# storage_board.net
KiCad netlist of a schematic drawn in EAGLE
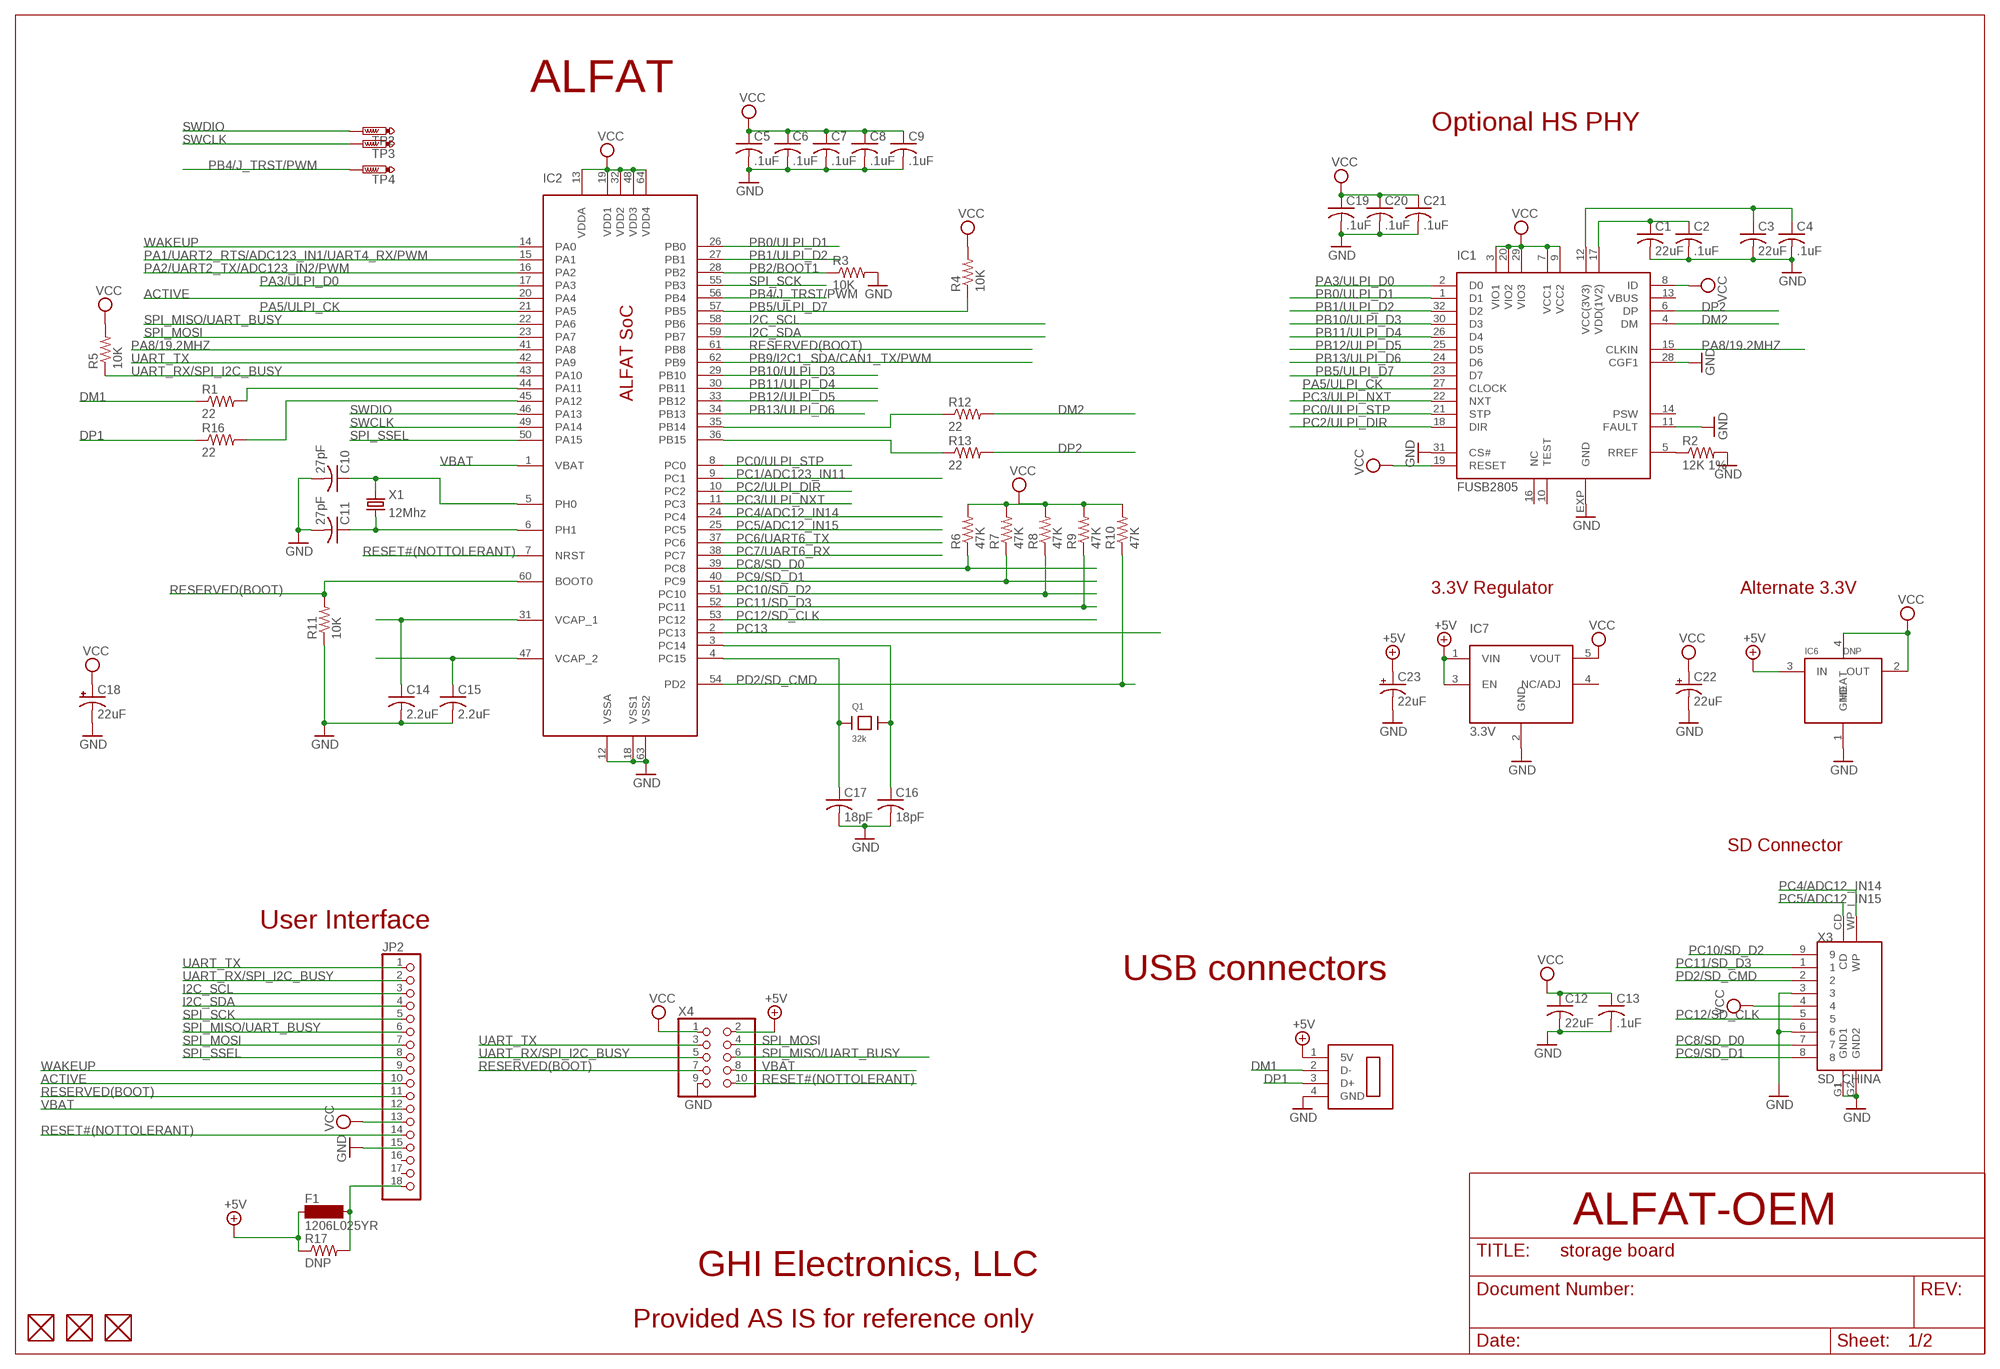
[diagram p0: schematic, sheet 1]
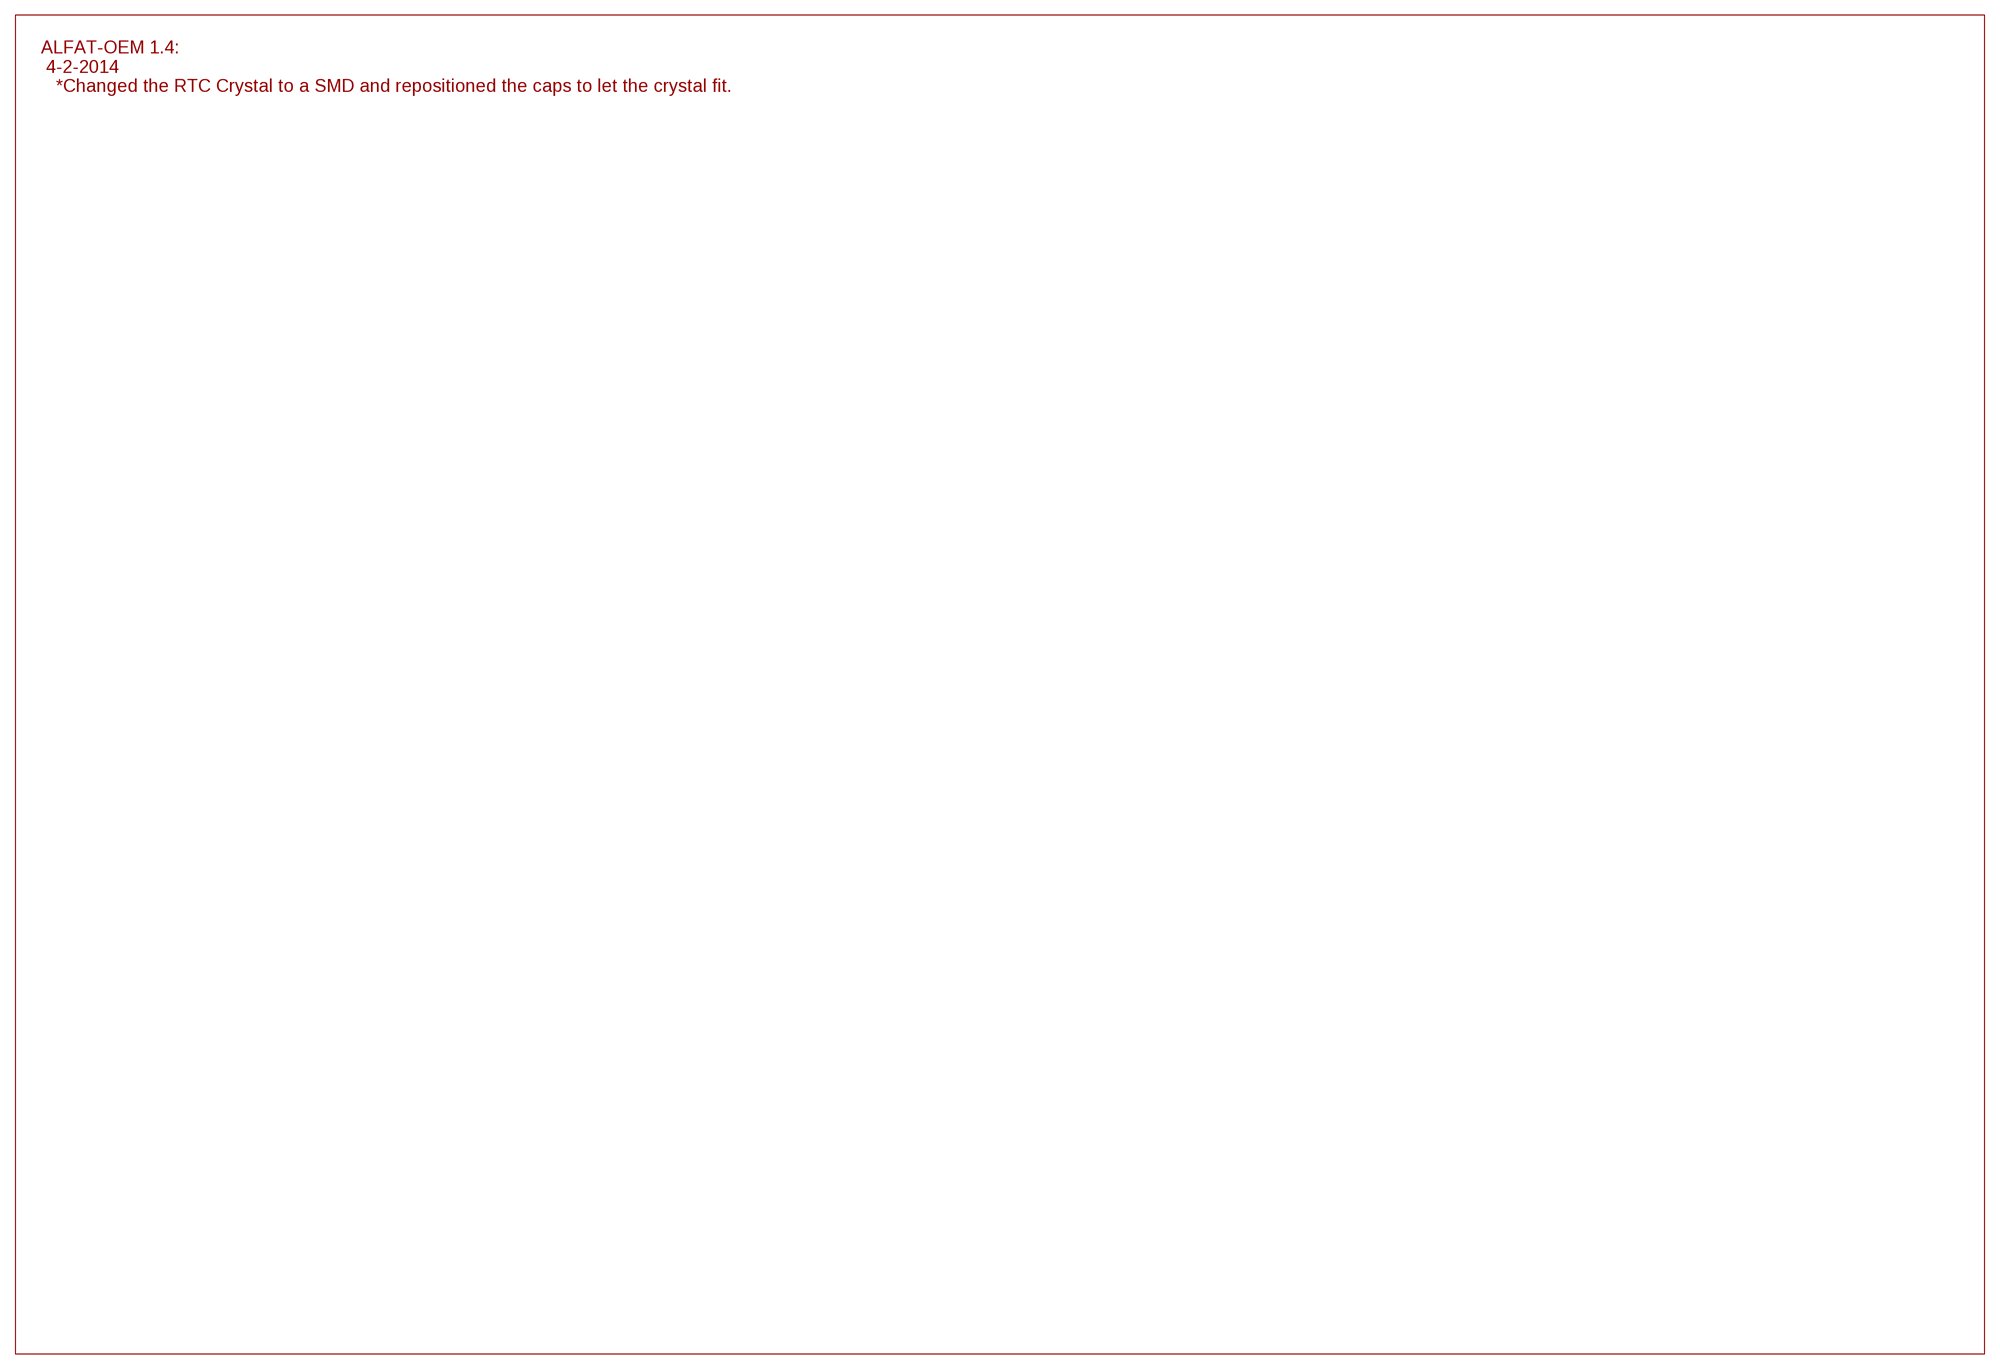
[diagram p1: schematic, sheet 2]

(export (version "E")
  (design (tool "Eeschema 10.0.6"))
  (components
    (comp (ref "C1")
      (value "22uF")
      (footprint "eagle-import:C0805K")
      (libsource (lib "eagle-import") (part "C-USC0805K"))
    )
    (comp (ref "C2")
      (value ".1uF")
      (footprint "eagle-import:C0603K")
      (libsource (lib "eagle-import") (part "C-USC0603K"))
    )
    (comp (ref "C3")
      (value "22uF")
      (footprint "eagle-import:C0805K")
      (libsource (lib "eagle-import") (part "C-USC0805K"))
    )
    (comp (ref "C4")
      (value ".1uF")
      (footprint "eagle-import:C0603K")
      (libsource (lib "eagle-import") (part "C-USC0603K"))
    )
    (comp (ref "C5")
      (value ".1uF")
      (footprint "eagle-import:C0603K")
      (libsource (lib "eagle-import") (part "C-USC0603K"))
    )
    (comp (ref "C6")
      (value ".1uF")
      (footprint "eagle-import:C0603K")
      (libsource (lib "eagle-import") (part "C-USC0603K"))
    )
    (comp (ref "C7")
      (value ".1uF")
      (footprint "eagle-import:C0603K")
      (libsource (lib "eagle-import") (part "C-USC0603K"))
    )
    (comp (ref "C8")
      (value ".1uF")
      (footprint "eagle-import:C0603K")
      (libsource (lib "eagle-import") (part "C-USC0603K"))
    )
    (comp (ref "C9")
      (value ".1uF")
      (footprint "eagle-import:C0603K")
      (libsource (lib "eagle-import") (part "C-USC0603K"))
    )
    (comp (ref "C10")
      (value "27pF")
      (footprint "eagle-import:C0603K")
      (libsource (lib "eagle-import") (part "C-USC0603K"))
    )
    (comp (ref "C11")
      (value "27pF")
      (footprint "eagle-import:C0603K")
      (libsource (lib "eagle-import") (part "C-USC0603K"))
    )
    (comp (ref "C12")
      (value "22uF")
      (footprint "eagle-import:C0805K")
      (libsource (lib "eagle-import") (part "C-USC0805K"))
    )
    (comp (ref "C13")
      (value ".1uF")
      (footprint "eagle-import:C0603K")
      (libsource (lib "eagle-import") (part "C-USC0603K"))
    )
    (comp (ref "C14")
      (value "2.2uF")
      (footprint "eagle-import:C0805K")
      (libsource (lib "eagle-import") (part "C-USC0805K"))
    )
    (comp (ref "C15")
      (value "2.2uF")
      (footprint "eagle-import:C0805K")
      (libsource (lib "eagle-import") (part "C-USC0805K"))
    )
    (comp (ref "C16")
      (value "18pF")
      (footprint "eagle-import:C0603K")
      (libsource (lib "eagle-import") (part "C-USC0603K"))
    )
    (comp (ref "C17")
      (value "18pF")
      (footprint "eagle-import:C0603K")
      (libsource (lib "eagle-import") (part "C-USC0603K"))
    )
    (comp (ref "C18")
      (value "22uF")
      (footprint "eagle-import:CT3528")
      (libsource (lib "eagle-import") (part "CPOL-USCT3528"))
    )
    (comp (ref "C19")
      (value ".1uF")
      (footprint "eagle-import:C0603K")
      (libsource (lib "eagle-import") (part "C-USC0603K"))
    )
    (comp (ref "C20")
      (value ".1uF")
      (footprint "eagle-import:C0603K")
      (libsource (lib "eagle-import") (part "C-USC0603K"))
    )
    (comp (ref "C21")
      (value ".1uF")
      (footprint "eagle-import:C0603K")
      (libsource (lib "eagle-import") (part "C-USC0603K"))
    )
    (comp (ref "C22")
      (value "22uF")
      (footprint "eagle-import:CT3528")
      (libsource (lib "eagle-import") (part "CPOL-USCT3528"))
    )
    (comp (ref "C23")
      (value "22uF")
      (footprint "eagle-import:CT3528")
      (libsource (lib "eagle-import") (part "CPOL-USCT3528"))
    )
    (comp (ref "F1")
      (value "1206L025YR")
      (footprint "eagle-import:SM-1206")
      (libsource (lib "eagle-import") (part "SM-1206"))
    )
    (comp (ref "FUD1")
      (value "FIDUCIAL")
      (footprint "eagle-import:FIDUCIAL_40MIL")
      (libsource (lib "eagle-import") (part "FIDUCIAL"))
    )
    (comp (ref "FUD2")
      (value "FIDUCIAL")
      (footprint "eagle-import:FIDUCIAL_40MIL")
      (libsource (lib "eagle-import") (part "FIDUCIAL"))
    )
    (comp (ref "FUD3")
      (value "FIDUCIAL")
      (footprint "eagle-import:FIDUCIAL_40MIL")
      (libsource (lib "eagle-import") (part "FIDUCIAL"))
    )
    (comp (ref "IC1")
      (value "FUSB2805")
      (footprint "eagle-import:MLP32")
      (libsource (lib "eagle-import") (part "FUSB2805"))
    )
    (comp (ref "IC2")
      (value "STM32F40X")
      (footprint "eagle-import:LQFP64")
      (libsource (lib "eagle-import") (part "STM32F40X"))
    )
    (comp (ref "IC6")
      (value "DNP")
      (footprint "eagle-import:SOT89")
      (libsource (lib "eagle-import") (part "LD1117SOT89"))
    )
    (comp (ref "IC7")
      (value "3.3V")
      (footprint "eagle-import:SOT23-5")
      (libsource (lib "eagle-import") (part "5PIN_REG"))
    )
    (comp (ref "JP2")
      (value "PINHD-1X18")
      (footprint "eagle-import:1X18")
      (libsource (lib "eagle-import") (part "PINHD-1X18"))
    )
    (comp (ref "Q1")
      (value "32k")
      (footprint "eagle-import:CRYSTAL_3.2X1.5")
      (libsource (lib "eagle-import") (part "CRYSTAL_3.2X1.5"))
    )
    (comp (ref "R1")
      (value "22")
      (footprint "eagle-import:R0603")
      (libsource (lib "eagle-import") (part "R-US_R0603"))
    )
    (comp (ref "R2")
      (value "12K 1%")
      (footprint "eagle-import:R0603")
      (libsource (lib "eagle-import") (part "R-US_R0603"))
    )
    (comp (ref "R3")
      (value "10K")
      (footprint "eagle-import:R0603")
      (libsource (lib "eagle-import") (part "R-US_R0603"))
    )
    (comp (ref "R4")
      (value "10K")
      (footprint "eagle-import:R0603")
      (libsource (lib "eagle-import") (part "R-US_R0603"))
    )
    (comp (ref "R5")
      (value "10K")
      (footprint "eagle-import:R0603")
      (libsource (lib "eagle-import") (part "R-US_R0603"))
    )
    (comp (ref "R6")
      (value "47K")
      (footprint "eagle-import:R0603")
      (libsource (lib "eagle-import") (part "R-US_R0603"))
    )
    (comp (ref "R7")
      (value "47K")
      (footprint "eagle-import:R0603")
      (libsource (lib "eagle-import") (part "R-US_R0603"))
    )
    (comp (ref "R8")
      (value "47K")
      (footprint "eagle-import:R0603")
      (libsource (lib "eagle-import") (part "R-US_R0603"))
    )
    (comp (ref "R9")
      (value "47K")
      (footprint "eagle-import:R0603")
      (libsource (lib "eagle-import") (part "R-US_R0603"))
    )
    (comp (ref "R10")
      (value "47K")
      (footprint "eagle-import:R0603")
      (libsource (lib "eagle-import") (part "R-US_R0603"))
    )
    (comp (ref "R11")
      (value "10K")
      (footprint "eagle-import:R0603")
      (libsource (lib "eagle-import") (part "R-US_R0603"))
    )
    (comp (ref "R12")
      (value "22")
      (footprint "eagle-import:R0603")
      (libsource (lib "eagle-import") (part "R-US_R0603"))
    )
    (comp (ref "R13")
      (value "22")
      (footprint "eagle-import:R0603")
      (libsource (lib "eagle-import") (part "R-US_R0603"))
    )
    (comp (ref "R16")
      (value "22")
      (footprint "eagle-import:R0603")
      (libsource (lib "eagle-import") (part "R-US_R0603"))
    )
    (comp (ref "R17")
      (value "DNP")
      (footprint "eagle-import:R0603")
      (libsource (lib "eagle-import") (part "R-US_R0603"))
    )
    (comp (ref "TP2")
      (value "PTR1B1,27")
      (footprint "eagle-import:B1,27")
      (libsource (lib "eagle-import") (part "PTR1B1,27"))
    )
    (comp (ref "TP3")
      (value "PTR1B1,27")
      (footprint "eagle-import:B1,27")
      (libsource (lib "eagle-import") (part "PTR1B1,27"))
    )
    (comp (ref "TP4")
      (value "PTR1B1,27")
      (footprint "eagle-import:B1,27")
      (libsource (lib "eagle-import") (part "PTR1B1,27"))
    )
    (comp (ref "X1")
      (value "12Mhz")
      (footprint "eagle-import:SM49@1")
      (libsource (lib "eagle-import") (part "CRYTALSM49"))
    )
    (comp (ref "X2")
      (value "USB_HOST_CON")
      (footprint "eagle-import:USB_HOST_CON")
      (libsource (lib "eagle-import") (part "USB_HOST_CON"))
    )
    (comp (ref "X3")
      (value "SD_CHINA")
      (footprint "eagle-import:SD_CHINA")
      (libsource (lib "eagle-import") (part "SD_CHINA"))
    )
    (comp (ref "X4")
      (value "PINHD-2X5")
      (footprint "eagle-import:2X05")
      (libsource (lib "eagle-import") (part "PINHD-2X5"))
    )
  )
  (nets
    (net (code "1") (name "+5V") (class "Default")
      (node (ref "C23") (pin "+") (pinfunction "+_+") (pintype "passive"))
      (node (ref "F1") (pin "1") (pinfunction "1_1") (pintype "passive"))
      (node (ref "IC6") (pin "3") (pinfunction "IN_3") (pintype "bidirectional"))
      (node (ref "IC7") (pin "1") (pinfunction "VIN_1") (pintype "bidirectional"))
      (node (ref "IC7") (pin "3") (pinfunction "EN_3") (pintype "bidirectional"))
      (node (ref "R17") (pin "1") (pinfunction "1_1") (pintype "passive"))
      (node (ref "X2") (pin "1") (pinfunction "5V_1") (pintype "input"))
      (node (ref "X4") (pin "2") (pinfunction "2_2") (pintype "passive"))
    )
    (net (code "2") (name "ACTIVE") (class "Default")
      (node (ref "IC2") (pin "20") (pinfunction "PA4_20") (pintype "bidirectional"))
      (node (ref "JP2") (pin "10") (pinfunction "10_10") (pintype "passive"))
    )
    (net (code "3") (name "DM1") (class "Default")
      (node (ref "R1") (pin "1") (pinfunction "1_1") (pintype "passive"))
      (node (ref "X2") (pin "2") (pinfunction "D-_2") (pintype "bidirectional"))
    )
    (net (code "4") (name "DM2") (class "Default")
      (node (ref "IC1") (pin "4") (pinfunction "DM_4") (pintype "bidirectional"))
      (node (ref "R12") (pin "2") (pinfunction "2_2") (pintype "passive"))
    )
    (net (code "5") (name "DP1") (class "Default")
      (node (ref "R16") (pin "1") (pinfunction "1_1") (pintype "passive"))
      (node (ref "X2") (pin "3") (pinfunction "D+_3") (pintype "bidirectional"))
    )
    (net (code "6") (name "DP2") (class "Default")
      (node (ref "IC1") (pin "6") (pinfunction "DP_6") (pintype "bidirectional"))
      (node (ref "R13") (pin "2") (pinfunction "2_2") (pintype "passive"))
    )
    (net (code "7") (name "GND") (class "Default")
      (node (ref "C1") (pin "2") (pinfunction "2_2") (pintype "passive"))
      (node (ref "C10") (pin "2") (pinfunction "2_2") (pintype "passive"))
      (node (ref "C11") (pin "2") (pinfunction "2_2") (pintype "passive"))
      (node (ref "C12") (pin "2") (pinfunction "2_2") (pintype "passive"))
      (node (ref "C13") (pin "2") (pinfunction "2_2") (pintype "passive"))
      (node (ref "C14") (pin "2") (pinfunction "2_2") (pintype "passive"))
      (node (ref "C15") (pin "2") (pinfunction "2_2") (pintype "passive"))
      (node (ref "C16") (pin "2") (pinfunction "2_2") (pintype "passive"))
      (node (ref "C17") (pin "2") (pinfunction "2_2") (pintype "passive"))
      (node (ref "C18") (pin "-") (pinfunction "-_-") (pintype "passive"))
      (node (ref "C19") (pin "2") (pinfunction "2_2") (pintype "passive"))
      (node (ref "C2") (pin "2") (pinfunction "2_2") (pintype "passive"))
      (node (ref "C20") (pin "2") (pinfunction "2_2") (pintype "passive"))
      (node (ref "C21") (pin "2") (pinfunction "2_2") (pintype "passive"))
      (node (ref "C22") (pin "-") (pinfunction "-_-") (pintype "passive"))
      (node (ref "C23") (pin "-") (pinfunction "-_-") (pintype "passive"))
      (node (ref "C3") (pin "2") (pinfunction "2_2") (pintype "passive"))
      (node (ref "C4") (pin "2") (pinfunction "2_2") (pintype "passive"))
      (node (ref "C5") (pin "2") (pinfunction "2_2") (pintype "passive"))
      (node (ref "C6") (pin "2") (pinfunction "2_2") (pintype "passive"))
      (node (ref "C7") (pin "2") (pinfunction "2_2") (pintype "passive"))
      (node (ref "C8") (pin "2") (pinfunction "2_2") (pintype "passive"))
      (node (ref "C9") (pin "2") (pinfunction "2_2") (pintype "passive"))
      (node (ref "IC1") (pin "11") (pinfunction "FAULT_11") (pintype "bidirectional"))
      (node (ref "IC1") (pin "28") (pinfunction "CGF1_28") (pintype "bidirectional"))
      (node (ref "IC1") (pin "31") (pinfunction "CS#_31") (pintype "bidirectional"))
      (node (ref "IC1") (pin "EXP") (pinfunction "GND_EXP") (pintype "bidirectional"))
      (node (ref "IC2") (pin "12") (pinfunction "VSSA_12") (pintype "bidirectional"))
      (node (ref "IC2") (pin "18") (pinfunction "VSS1_18") (pintype "bidirectional"))
      (node (ref "IC2") (pin "63") (pinfunction "VSS2_63") (pintype "bidirectional"))
      (node (ref "IC6") (pin "1") (pinfunction "GND_1") (pintype "bidirectional"))
      (node (ref "IC7") (pin "2") (pinfunction "GND_2") (pintype "bidirectional"))
      (node (ref "JP2") (pin "15") (pinfunction "15_15") (pintype "passive"))
      (node (ref "R11") (pin "1") (pinfunction "1_1") (pintype "passive"))
      (node (ref "R2") (pin "2") (pinfunction "2_2") (pintype "passive"))
      (node (ref "R3") (pin "2") (pinfunction "2_2") (pintype "passive"))
      (node (ref "X2") (pin "4") (pinfunction "GND_4") (pintype "power_in"))
      (node (ref "X3") (pin "3") (pinfunction "3_3") (pintype "bidirectional"))
      (node (ref "X3") (pin "6") (pinfunction "6_6") (pintype "bidirectional"))
      (node (ref "X3") (pin "G1") (pinfunction "GND1_G1") (pintype "bidirectional"))
      (node (ref "X3") (pin "G2") (pinfunction "GND2_G2") (pintype "bidirectional"))
      (node (ref "X4") (pin "9") (pinfunction "9_9") (pintype "passive"))
    )
    (net (code "8") (name "I2C_SCL") (class "Default")
      (node (ref "IC2") (pin "58") (pinfunction "PB6_58") (pintype "bidirectional"))
      (node (ref "JP2") (pin "3") (pinfunction "3_3") (pintype "passive"))
    )
    (net (code "9") (name "I2C_SDA") (class "Default")
      (node (ref "IC2") (pin "59") (pinfunction "PB7_59") (pintype "bidirectional"))
      (node (ref "JP2") (pin "4") (pinfunction "4_4") (pintype "passive"))
    )
    (net (code "10") (name "Net-(F1-Pad2)") (class "Default")
      (node (ref "F1") (pin "2") (pinfunction "2_2") (pintype "passive"))
      (node (ref "JP2") (pin "18") (pinfunction "18_18") (pintype "passive"))
      (node (ref "R17") (pin "2") (pinfunction "2_2") (pintype "passive"))
    )
    (net (code "11") (name "Net-(IC1-RREF)") (class "Default")
      (node (ref "IC1") (pin "5") (pinfunction "RREF_5") (pintype "bidirectional"))
      (node (ref "R2") (pin "1") (pinfunction "1_1") (pintype "passive"))
    )
    (net (code "12") (name "Net-(IC1-VCC(3V3))") (class "Default")
      (node (ref "C3") (pin "1") (pinfunction "1_1") (pintype "passive"))
      (node (ref "C4") (pin "1") (pinfunction "1_1") (pintype "passive"))
      (node (ref "IC1") (pin "12") (pinfunction "VCC(3V3)_12") (pintype "bidirectional"))
    )
    (net (code "13") (name "Net-(IC1-VDD(1V2))") (class "Default")
      (node (ref "C1") (pin "1") (pinfunction "1_1") (pintype "passive"))
      (node (ref "C2") (pin "1") (pinfunction "1_1") (pintype "passive"))
      (node (ref "IC1") (pin "17") (pinfunction "VDD(1V2)_17") (pintype "bidirectional"))
    )
    (net (code "14") (name "Net-(IC2-PA11)") (class "Default")
      (node (ref "IC2") (pin "44") (pinfunction "PA11_44") (pintype "bidirectional"))
      (node (ref "R1") (pin "2") (pinfunction "2_2") (pintype "passive"))
    )
    (net (code "15") (name "Net-(IC2-PA12)") (class "Default")
      (node (ref "IC2") (pin "45") (pinfunction "PA12_45") (pintype "bidirectional"))
      (node (ref "R16") (pin "2") (pinfunction "2_2") (pintype "passive"))
    )
    (net (code "16") (name "Net-(IC2-PB14)") (class "Default")
      (node (ref "IC2") (pin "35") (pinfunction "PB14_35") (pintype "bidirectional"))
      (node (ref "R12") (pin "1") (pinfunction "1_1") (pintype "passive"))
    )
    (net (code "17") (name "Net-(IC2-PB15)") (class "Default")
      (node (ref "IC2") (pin "36") (pinfunction "PB15_36") (pintype "bidirectional"))
      (node (ref "R13") (pin "1") (pinfunction "1_1") (pintype "passive"))
    )
    (net (code "18") (name "Net-(IC2-PC14)") (class "Default")
      (node (ref "C16") (pin "1") (pinfunction "1_1") (pintype "passive"))
      (node (ref "IC2") (pin "3") (pinfunction "PC14_3") (pintype "bidirectional"))
      (node (ref "Q1") (pin "P$2") (pinfunction "P$2_P$2") (pintype "passive"))
    )
    (net (code "19") (name "Net-(IC2-PC15)") (class "Default")
      (node (ref "C17") (pin "1") (pinfunction "1_1") (pintype "passive"))
      (node (ref "IC2") (pin "4") (pinfunction "PC15_4") (pintype "bidirectional"))
      (node (ref "Q1") (pin "P$1") (pinfunction "P$1_P$1") (pintype "passive"))
    )
    (net (code "20") (name "Net-(IC2-PH0)") (class "Default")
      (node (ref "C10") (pin "1") (pinfunction "1_1") (pintype "passive"))
      (node (ref "IC2") (pin "5") (pinfunction "PH0_5") (pintype "bidirectional"))
      (node (ref "X1") (pin "2") (pinfunction "2_2") (pintype "passive"))
    )
    (net (code "21") (name "Net-(IC2-PH1)") (class "Default")
      (node (ref "C11") (pin "1") (pinfunction "1_1") (pintype "passive"))
      (node (ref "IC2") (pin "6") (pinfunction "PH1_6") (pintype "bidirectional"))
      (node (ref "X1") (pin "1") (pinfunction "1_1") (pintype "passive"))
    )
    (net (code "22") (name "Net-(IC2-VCAP_1)") (class "Default")
      (node (ref "C14") (pin "1") (pinfunction "1_1") (pintype "passive"))
      (node (ref "IC2") (pin "31") (pinfunction "VCAP_1_31") (pintype "bidirectional"))
    )
    (net (code "23") (name "Net-(IC2-VCAP_2)") (class "Default")
      (node (ref "C15") (pin "1") (pinfunction "1_1") (pintype "passive"))
      (node (ref "IC2") (pin "47") (pinfunction "VCAP_2_47") (pintype "bidirectional"))
    )
    (net (code "24") (name "PA1{slash}UART2_RTS{slash}ADC123_IN1{slash}UART4_RX{slash}PWM") (class "Default")
      (node (ref "IC2") (pin "15") (pinfunction "PA1_15") (pintype "bidirectional"))
    )
    (net (code "25") (name "PA2{slash}UART2_TX{slash}ADC123_IN2{slash}PWM") (class "Default")
      (node (ref "IC2") (pin "16") (pinfunction "PA2_16") (pintype "bidirectional"))
    )
    (net (code "26") (name "PA3{slash}ULPI_D0") (class "Default")
      (node (ref "IC1") (pin "2") (pinfunction "D0_2") (pintype "bidirectional"))
      (node (ref "IC2") (pin "17") (pinfunction "PA3_17") (pintype "bidirectional"))
    )
    (net (code "27") (name "PA5{slash}ULPI_CK") (class "Default")
      (node (ref "IC1") (pin "27") (pinfunction "CLOCK_27") (pintype "bidirectional"))
      (node (ref "IC2") (pin "21") (pinfunction "PA5_21") (pintype "bidirectional"))
    )
    (net (code "28") (name "PA8{slash}19.2MHZ") (class "Default")
      (node (ref "IC1") (pin "15") (pinfunction "CLKIN_15") (pintype "bidirectional"))
      (node (ref "IC2") (pin "41") (pinfunction "PA8_41") (pintype "bidirectional"))
    )
    (net (code "29") (name "PB0{slash}ULPI_D1") (class "Default")
      (node (ref "IC1") (pin "1") (pinfunction "D1_1") (pintype "bidirectional"))
      (node (ref "IC2") (pin "26") (pinfunction "PB0_26") (pintype "bidirectional"))
    )
    (net (code "30") (name "PB1{slash}ULPI_D2") (class "Default")
      (node (ref "IC1") (pin "32") (pinfunction "D2_32") (pintype "bidirectional"))
      (node (ref "IC2") (pin "27") (pinfunction "PB1_27") (pintype "bidirectional"))
    )
    (net (code "31") (name "PB2{slash}BOOT1") (class "Default")
      (node (ref "IC2") (pin "28") (pinfunction "PB2_28") (pintype "bidirectional"))
      (node (ref "R3") (pin "1") (pinfunction "1_1") (pintype "passive"))
    )
    (net (code "32") (name "PB4{slash}J_TRST{slash}PWM") (class "Default")
      (node (ref "IC2") (pin "56") (pinfunction "PB4_56") (pintype "bidirectional"))
      (node (ref "TP4") (pin "PP") (pinfunction "TP_PP") (pintype "input"))
    )
    (net (code "33") (name "PB5{slash}ULPI_D7") (class "Default")
      (node (ref "IC1") (pin "23") (pinfunction "D7_23") (pintype "bidirectional"))
      (node (ref "IC2") (pin "57") (pinfunction "PB5_57") (pintype "bidirectional"))
      (node (ref "R4") (pin "1") (pinfunction "1_1") (pintype "passive"))
    )
    (net (code "34") (name "PB9{slash}I2C1_SDA{slash}CAN1_TX{slash}PWM") (class "Default")
      (node (ref "IC2") (pin "62") (pinfunction "PB9_62") (pintype "bidirectional"))
    )
    (net (code "35") (name "PB10{slash}ULPI_D3") (class "Default")
      (node (ref "IC1") (pin "30") (pinfunction "D3_30") (pintype "bidirectional"))
      (node (ref "IC2") (pin "29") (pinfunction "PB10_29") (pintype "bidirectional"))
    )
    (net (code "36") (name "PB11{slash}ULPI_D4") (class "Default")
      (node (ref "IC1") (pin "26") (pinfunction "D4_26") (pintype "bidirectional"))
      (node (ref "IC2") (pin "30") (pinfunction "PB11_30") (pintype "bidirectional"))
    )
    (net (code "37") (name "PB12{slash}ULPI_D5") (class "Default")
      (node (ref "IC1") (pin "25") (pinfunction "D5_25") (pintype "bidirectional"))
      (node (ref "IC2") (pin "33") (pinfunction "PB12_33") (pintype "bidirectional"))
    )
    (net (code "38") (name "PB13{slash}ULPI_D6") (class "Default")
      (node (ref "IC1") (pin "24") (pinfunction "D6_24") (pintype "bidirectional"))
      (node (ref "IC2") (pin "34") (pinfunction "PB13_34") (pintype "bidirectional"))
    )
    (net (code "39") (name "PC0{slash}ULPI_STP") (class "Default")
      (node (ref "IC1") (pin "21") (pinfunction "STP_21") (pintype "bidirectional"))
      (node (ref "IC2") (pin "8") (pinfunction "PC0_8") (pintype "bidirectional"))
    )
    (net (code "40") (name "PC1{slash}ADC123_IN11") (class "Default")
      (node (ref "IC2") (pin "9") (pinfunction "PC1_9") (pintype "bidirectional"))
    )
    (net (code "41") (name "PC2{slash}ULPI_DIR") (class "Default")
      (node (ref "IC1") (pin "18") (pinfunction "DIR_18") (pintype "bidirectional"))
      (node (ref "IC2") (pin "10") (pinfunction "PC2_10") (pintype "bidirectional"))
    )
    (net (code "42") (name "PC3{slash}ULPI_NXT") (class "Default")
      (node (ref "IC1") (pin "22") (pinfunction "NXT_22") (pintype "bidirectional"))
      (node (ref "IC2") (pin "11") (pinfunction "PC3_11") (pintype "bidirectional"))
    )
    (net (code "43") (name "PC4{slash}ADC12_IN14") (class "Default")
      (node (ref "IC2") (pin "24") (pinfunction "PC4_24") (pintype "bidirectional"))
      (node (ref "X3") (pin "WP") (pinfunction "WP_WP") (pintype "bidirectional"))
    )
    (net (code "44") (name "PC5{slash}ADC12_IN15") (class "Default")
      (node (ref "IC2") (pin "25") (pinfunction "PC5_25") (pintype "bidirectional"))
      (node (ref "X3") (pin "CD") (pinfunction "CD_CD") (pintype "bidirectional"))
    )
    (net (code "45") (name "PC6{slash}UART6_TX") (class "Default")
      (node (ref "IC2") (pin "37") (pinfunction "PC6_37") (pintype "bidirectional"))
    )
    (net (code "46") (name "PC7{slash}UART6_RX") (class "Default")
      (node (ref "IC2") (pin "38") (pinfunction "PC7_38") (pintype "bidirectional"))
    )
    (net (code "47") (name "PC8{slash}SD_D0") (class "Default")
      (node (ref "IC2") (pin "39") (pinfunction "PC8_39") (pintype "bidirectional"))
      (node (ref "R6") (pin "1") (pinfunction "1_1") (pintype "passive"))
      (node (ref "X3") (pin "7") (pinfunction "7_7") (pintype "bidirectional"))
    )
    (net (code "48") (name "PC9{slash}SD_D1") (class "Default")
      (node (ref "IC2") (pin "40") (pinfunction "PC9_40") (pintype "bidirectional"))
      (node (ref "R7") (pin "1") (pinfunction "1_1") (pintype "passive"))
      (node (ref "X3") (pin "8") (pinfunction "8_8") (pintype "bidirectional"))
    )
    (net (code "49") (name "PC10{slash}SD_D2") (class "Default")
      (node (ref "IC2") (pin "51") (pinfunction "PC10_51") (pintype "bidirectional"))
      (node (ref "R8") (pin "1") (pinfunction "1_1") (pintype "passive"))
      (node (ref "X3") (pin "9") (pinfunction "9_9") (pintype "bidirectional"))
    )
    (net (code "50") (name "PC11{slash}SD_D3") (class "Default")
      (node (ref "IC2") (pin "52") (pinfunction "PC11_52") (pintype "bidirectional"))
      (node (ref "R9") (pin "1") (pinfunction "1_1") (pintype "passive"))
      (node (ref "X3") (pin "1") (pinfunction "1_1") (pintype "bidirectional"))
    )
    (net (code "51") (name "PC12{slash}SD_CLK") (class "Default")
      (node (ref "IC2") (pin "53") (pinfunction "PC12_53") (pintype "bidirectional"))
      (node (ref "X3") (pin "5") (pinfunction "5_5") (pintype "bidirectional"))
    )
    (net (code "52") (name "PC13") (class "Default")
      (node (ref "IC2") (pin "2") (pinfunction "PC13_2") (pintype "bidirectional"))
    )
    (net (code "53") (name "PD2{slash}SD_CMD") (class "Default")
      (node (ref "IC2") (pin "54") (pinfunction "PD2_54") (pintype "bidirectional"))
      (node (ref "R10") (pin "1") (pinfunction "1_1") (pintype "passive"))
      (node (ref "X3") (pin "2") (pinfunction "2_2") (pintype "bidirectional"))
    )
    (net (code "54") (name "RESERVED(BOOT)") (class "Default")
      (node (ref "IC2") (pin "60") (pinfunction "BOOT0_60") (pintype "bidirectional"))
      (node (ref "IC2") (pin "61") (pinfunction "PB8_61") (pintype "bidirectional"))
      (node (ref "JP2") (pin "11") (pinfunction "11_11") (pintype "passive"))
      (node (ref "R11") (pin "2") (pinfunction "2_2") (pintype "passive"))
      (node (ref "X4") (pin "7") (pinfunction "7_7") (pintype "passive"))
    )
    (net (code "55") (name "RESET#(NOTTOLERANT)") (class "Default")
      (node (ref "IC2") (pin "7") (pinfunction "NRST_7") (pintype "bidirectional"))
      (node (ref "JP2") (pin "14") (pinfunction "14_14") (pintype "passive"))
      (node (ref "X4") (pin "10") (pinfunction "10_10") (pintype "passive"))
    )
    (net (code "56") (name "SPI_MISO{slash}UART_BUSY") (class "Default")
      (node (ref "IC2") (pin "22") (pinfunction "PA6_22") (pintype "bidirectional"))
      (node (ref "JP2") (pin "6") (pinfunction "6_6") (pintype "passive"))
      (node (ref "X4") (pin "6") (pinfunction "6_6") (pintype "passive"))
    )
    (net (code "57") (name "SPI_MOSI") (class "Default")
      (node (ref "IC2") (pin "23") (pinfunction "PA7_23") (pintype "bidirectional"))
      (node (ref "JP2") (pin "7") (pinfunction "7_7") (pintype "passive"))
      (node (ref "X4") (pin "4") (pinfunction "4_4") (pintype "passive"))
    )
    (net (code "58") (name "SPI_SCK") (class "Default")
      (node (ref "IC2") (pin "55") (pinfunction "PB3_55") (pintype "bidirectional"))
      (node (ref "JP2") (pin "5") (pinfunction "5_5") (pintype "passive"))
    )
    (net (code "59") (name "SPI_SSEL") (class "Default")
      (node (ref "IC2") (pin "50") (pinfunction "PA15_50") (pintype "bidirectional"))
      (node (ref "JP2") (pin "8") (pinfunction "8_8") (pintype "passive"))
    )
    (net (code "60") (name "SWCLK") (class "Default")
      (node (ref "IC2") (pin "49") (pinfunction "PA14_49") (pintype "bidirectional"))
      (node (ref "TP3") (pin "PP") (pinfunction "TP_PP") (pintype "input"))
    )
    (net (code "61") (name "SWDIO") (class "Default")
      (node (ref "IC2") (pin "46") (pinfunction "PA13_46") (pintype "bidirectional"))
      (node (ref "TP2") (pin "PP") (pinfunction "TP_PP") (pintype "input"))
    )
    (net (code "62") (name "UART_RX{slash}SPI_I2C_BUSY") (class "Default")
      (node (ref "IC2") (pin "43") (pinfunction "PA10_43") (pintype "bidirectional"))
      (node (ref "JP2") (pin "2") (pinfunction "2_2") (pintype "passive"))
      (node (ref "R5") (pin "1") (pinfunction "1_1") (pintype "passive"))
      (node (ref "X4") (pin "5") (pinfunction "5_5") (pintype "passive"))
    )
    (net (code "63") (name "UART_TX") (class "Default")
      (node (ref "IC2") (pin "42") (pinfunction "PA9_42") (pintype "bidirectional"))
      (node (ref "JP2") (pin "1") (pinfunction "1_1") (pintype "passive"))
      (node (ref "X4") (pin "3") (pinfunction "3_3") (pintype "passive"))
    )
    (net (code "64") (name "VBAT") (class "Default")
      (node (ref "IC2") (pin "1") (pinfunction "VBAT_1") (pintype "bidirectional"))
      (node (ref "JP2") (pin "12") (pinfunction "12_12") (pintype "passive"))
      (node (ref "X4") (pin "8") (pinfunction "8_8") (pintype "passive"))
    )
    (net (code "65") (name "VCC") (class "Default")
      (node (ref "C12") (pin "1") (pinfunction "1_1") (pintype "passive"))
      (node (ref "C13") (pin "1") (pinfunction "1_1") (pintype "passive"))
      (node (ref "C18") (pin "+") (pinfunction "+_+") (pintype "passive"))
      (node (ref "C19") (pin "1") (pinfunction "1_1") (pintype "passive"))
      (node (ref "C20") (pin "1") (pinfunction "1_1") (pintype "passive"))
      (node (ref "C21") (pin "1") (pinfunction "1_1") (pintype "passive"))
      (node (ref "C22") (pin "+") (pinfunction "+_+") (pintype "passive"))
      (node (ref "C5") (pin "1") (pinfunction "1_1") (pintype "passive"))
      (node (ref "C6") (pin "1") (pinfunction "1_1") (pintype "passive"))
      (node (ref "C7") (pin "1") (pinfunction "1_1") (pintype "passive"))
      (node (ref "C8") (pin "1") (pinfunction "1_1") (pintype "passive"))
      (node (ref "C9") (pin "1") (pinfunction "1_1") (pintype "passive"))
      (node (ref "IC1") (pin "19") (pinfunction "RESET_19") (pintype "bidirectional"))
      (node (ref "IC1") (pin "20") (pinfunction "VIO2_20") (pintype "bidirectional"))
      (node (ref "IC1") (pin "29") (pinfunction "VIO3_29") (pintype "bidirectional"))
      (node (ref "IC1") (pin "3") (pinfunction "VIO1_3") (pintype "bidirectional"))
      (node (ref "IC1") (pin "7") (pinfunction "VCC1_7") (pintype "bidirectional"))
      (node (ref "IC1") (pin "8") (pinfunction "ID_8") (pintype "bidirectional"))
      (node (ref "IC1") (pin "9") (pinfunction "VCC2_9") (pintype "bidirectional"))
      (node (ref "IC2") (pin "13") (pinfunction "VDDA_13") (pintype "bidirectional"))
      (node (ref "IC2") (pin "19") (pinfunction "VDD1_19") (pintype "bidirectional"))
      (node (ref "IC2") (pin "32") (pinfunction "VDD2_32") (pintype "bidirectional"))
      (node (ref "IC2") (pin "48") (pinfunction "VDD3_48") (pintype "bidirectional"))
      (node (ref "IC2") (pin "64") (pinfunction "VDD4_64") (pintype "bidirectional"))
      (node (ref "IC6") (pin "2") (pinfunction "OUT_2") (pintype "bidirectional"))
      (node (ref "IC6") (pin "4") (pinfunction "HEAT_4") (pintype "bidirectional"))
      (node (ref "IC7") (pin "5") (pinfunction "VOUT_5") (pintype "bidirectional"))
      (node (ref "JP2") (pin "13") (pinfunction "13_13") (pintype "passive"))
      (node (ref "R10") (pin "2") (pinfunction "2_2") (pintype "passive"))
      (node (ref "R4") (pin "2") (pinfunction "2_2") (pintype "passive"))
      (node (ref "R5") (pin "2") (pinfunction "2_2") (pintype "passive"))
      (node (ref "R6") (pin "2") (pinfunction "2_2") (pintype "passive"))
      (node (ref "R7") (pin "2") (pinfunction "2_2") (pintype "passive"))
      (node (ref "R8") (pin "2") (pinfunction "2_2") (pintype "passive"))
      (node (ref "R9") (pin "2") (pinfunction "2_2") (pintype "passive"))
      (node (ref "X3") (pin "4") (pinfunction "4_4") (pintype "bidirectional"))
      (node (ref "X4") (pin "1") (pinfunction "1_1") (pintype "passive"))
    )
    (net (code "66") (name "WAKEUP") (class "Default")
      (node (ref "IC2") (pin "14") (pinfunction "PA0_14") (pintype "bidirectional"))
      (node (ref "JP2") (pin "9") (pinfunction "9_9") (pintype "passive"))
    )
    (net (code "67") (name "unconnected-(FUD1-PadP$1)") (class "Default")
      (node (ref "FUD1") (pin "P$1") (pinfunction "P$1_P$1") (pintype "no_connect"))
    )
    (net (code "68") (name "unconnected-(FUD2-PadP$1)") (class "Default")
      (node (ref "FUD2") (pin "P$1") (pinfunction "P$1_P$1") (pintype "no_connect"))
    )
    (net (code "69") (name "unconnected-(FUD3-PadP$1)") (class "Default")
      (node (ref "FUD3") (pin "P$1") (pinfunction "P$1_P$1") (pintype "no_connect"))
    )
    (net (code "70") (name "unconnected-(IC1-NC-Pad16)") (class "Default")
      (node (ref "IC1") (pin "16") (pinfunction "NC_16") (pintype "bidirectional"))
    )
    (net (code "71") (name "unconnected-(IC1-PSW-Pad14)") (class "Default")
      (node (ref "IC1") (pin "14") (pinfunction "PSW_14") (pintype "bidirectional"))
    )
    (net (code "72") (name "unconnected-(IC1-TEST-Pad10)") (class "Default")
      (node (ref "IC1") (pin "10") (pinfunction "TEST_10") (pintype "bidirectional"))
    )
    (net (code "73") (name "unconnected-(IC1-VBUS-Pad13)") (class "Default")
      (node (ref "IC1") (pin "13") (pinfunction "VBUS_13") (pintype "bidirectional"))
    )
    (net (code "74") (name "unconnected-(IC7-NC{slash}ADJ-Pad4)") (class "Default")
      (node (ref "IC7") (pin "4") (pinfunction "NC/ADJ_4") (pintype "bidirectional"))
    )
    (net (code "75") (name "unconnected-(JP2-Pad16)") (class "Default")
      (node (ref "JP2") (pin "16") (pinfunction "16_16") (pintype "passive"))
    )
    (net (code "76") (name "unconnected-(JP2-Pad17)") (class "Default")
      (node (ref "JP2") (pin "17") (pinfunction "17_17") (pintype "passive"))
    )
  )
)
